# MorphingVCA.net
KiCad netlist of a schematic drawn in EAGLE
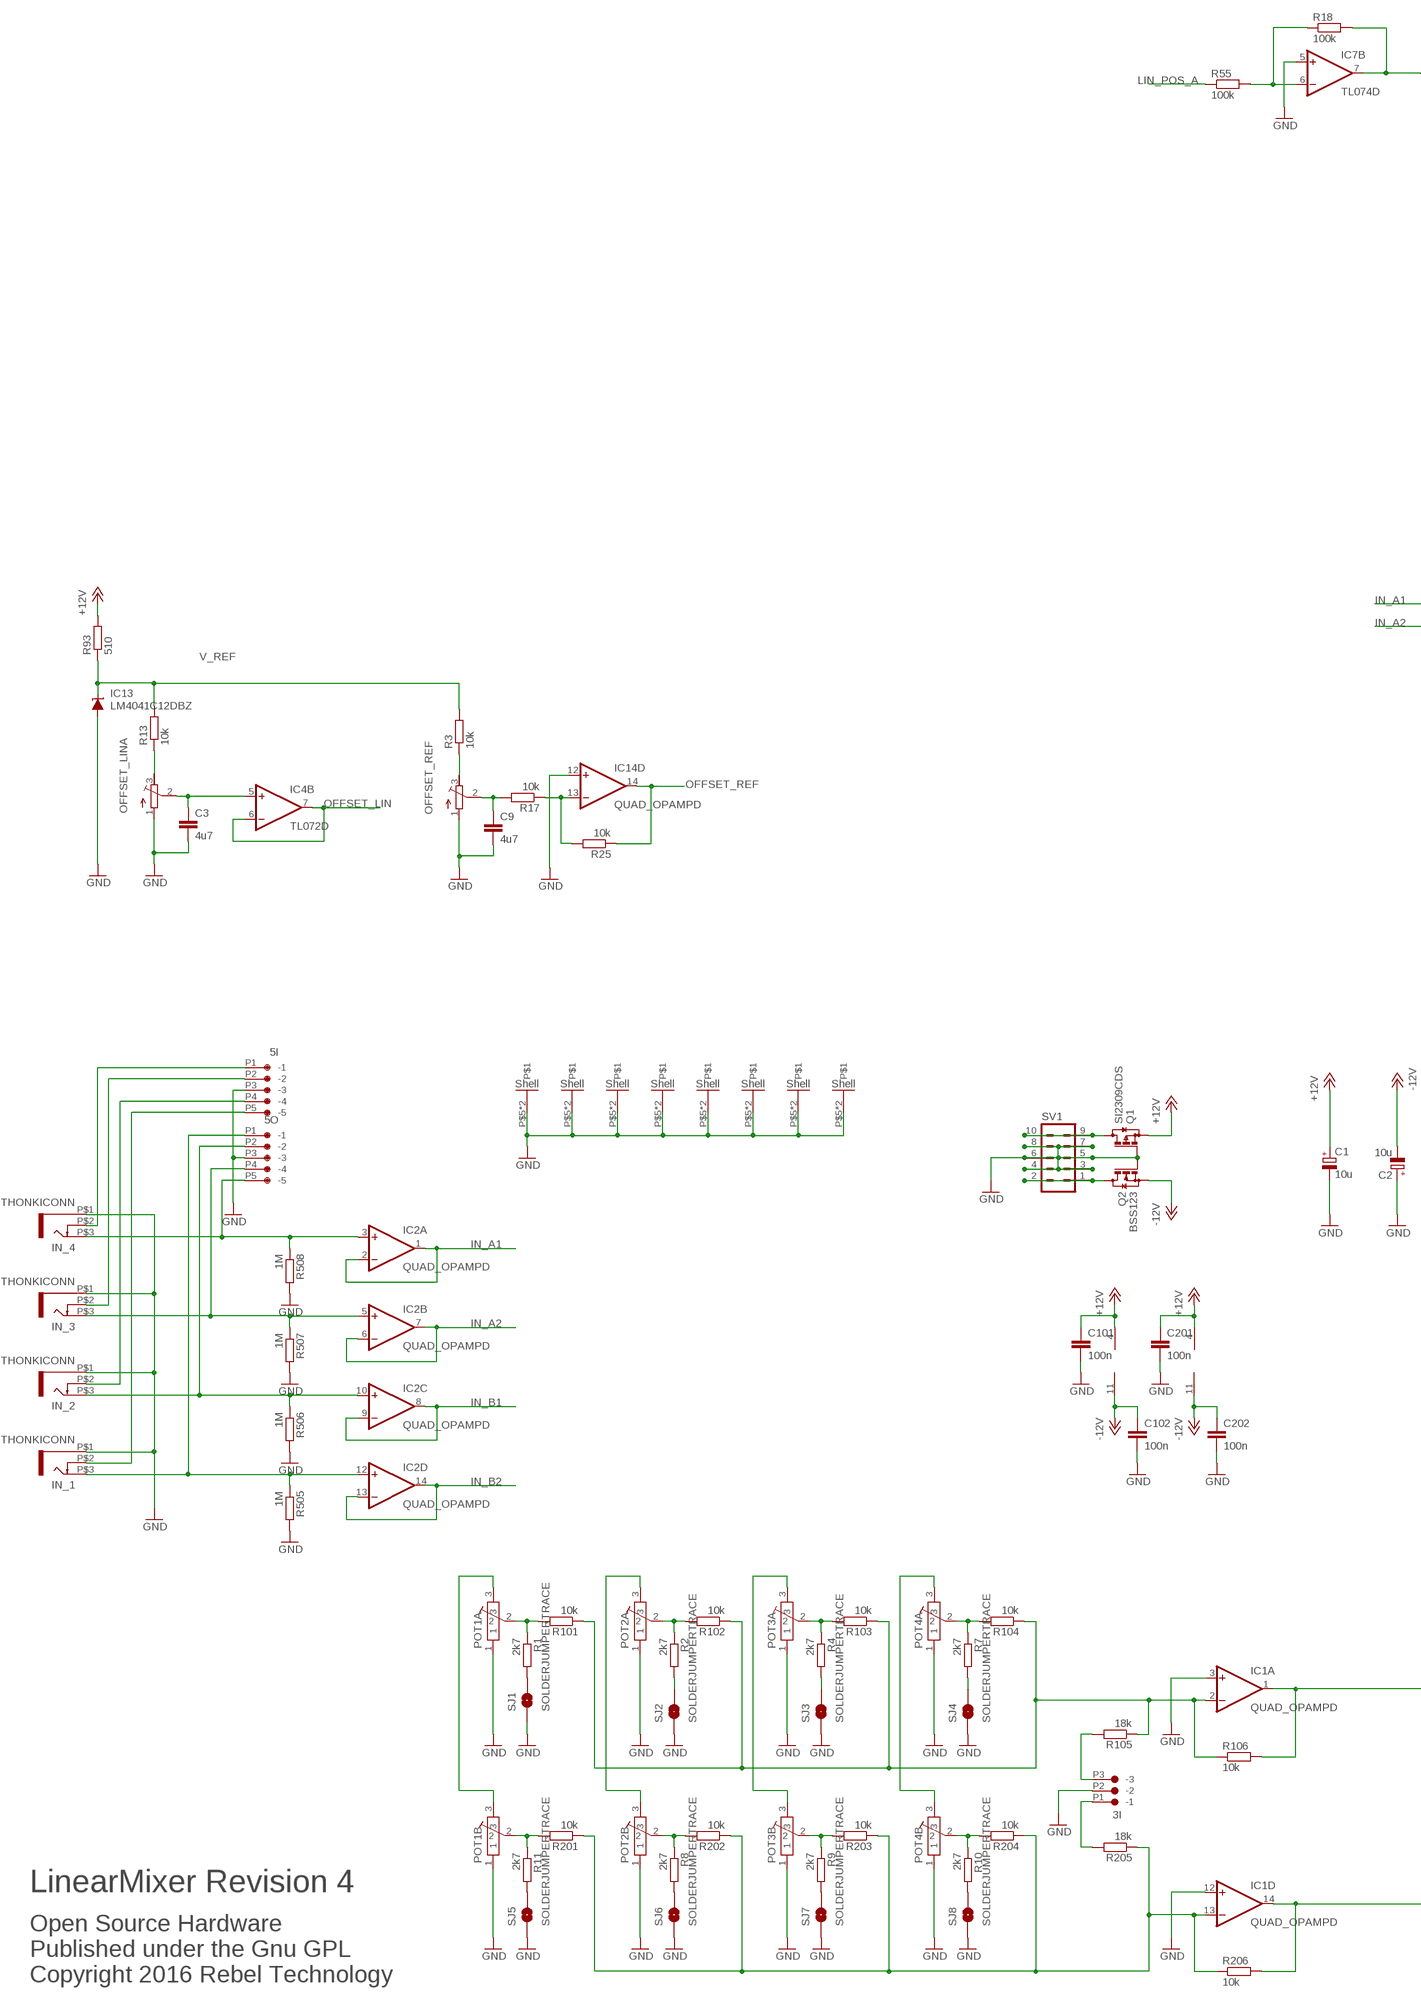
[diagram p0: schematic, sheet 1, part 1 of 2]
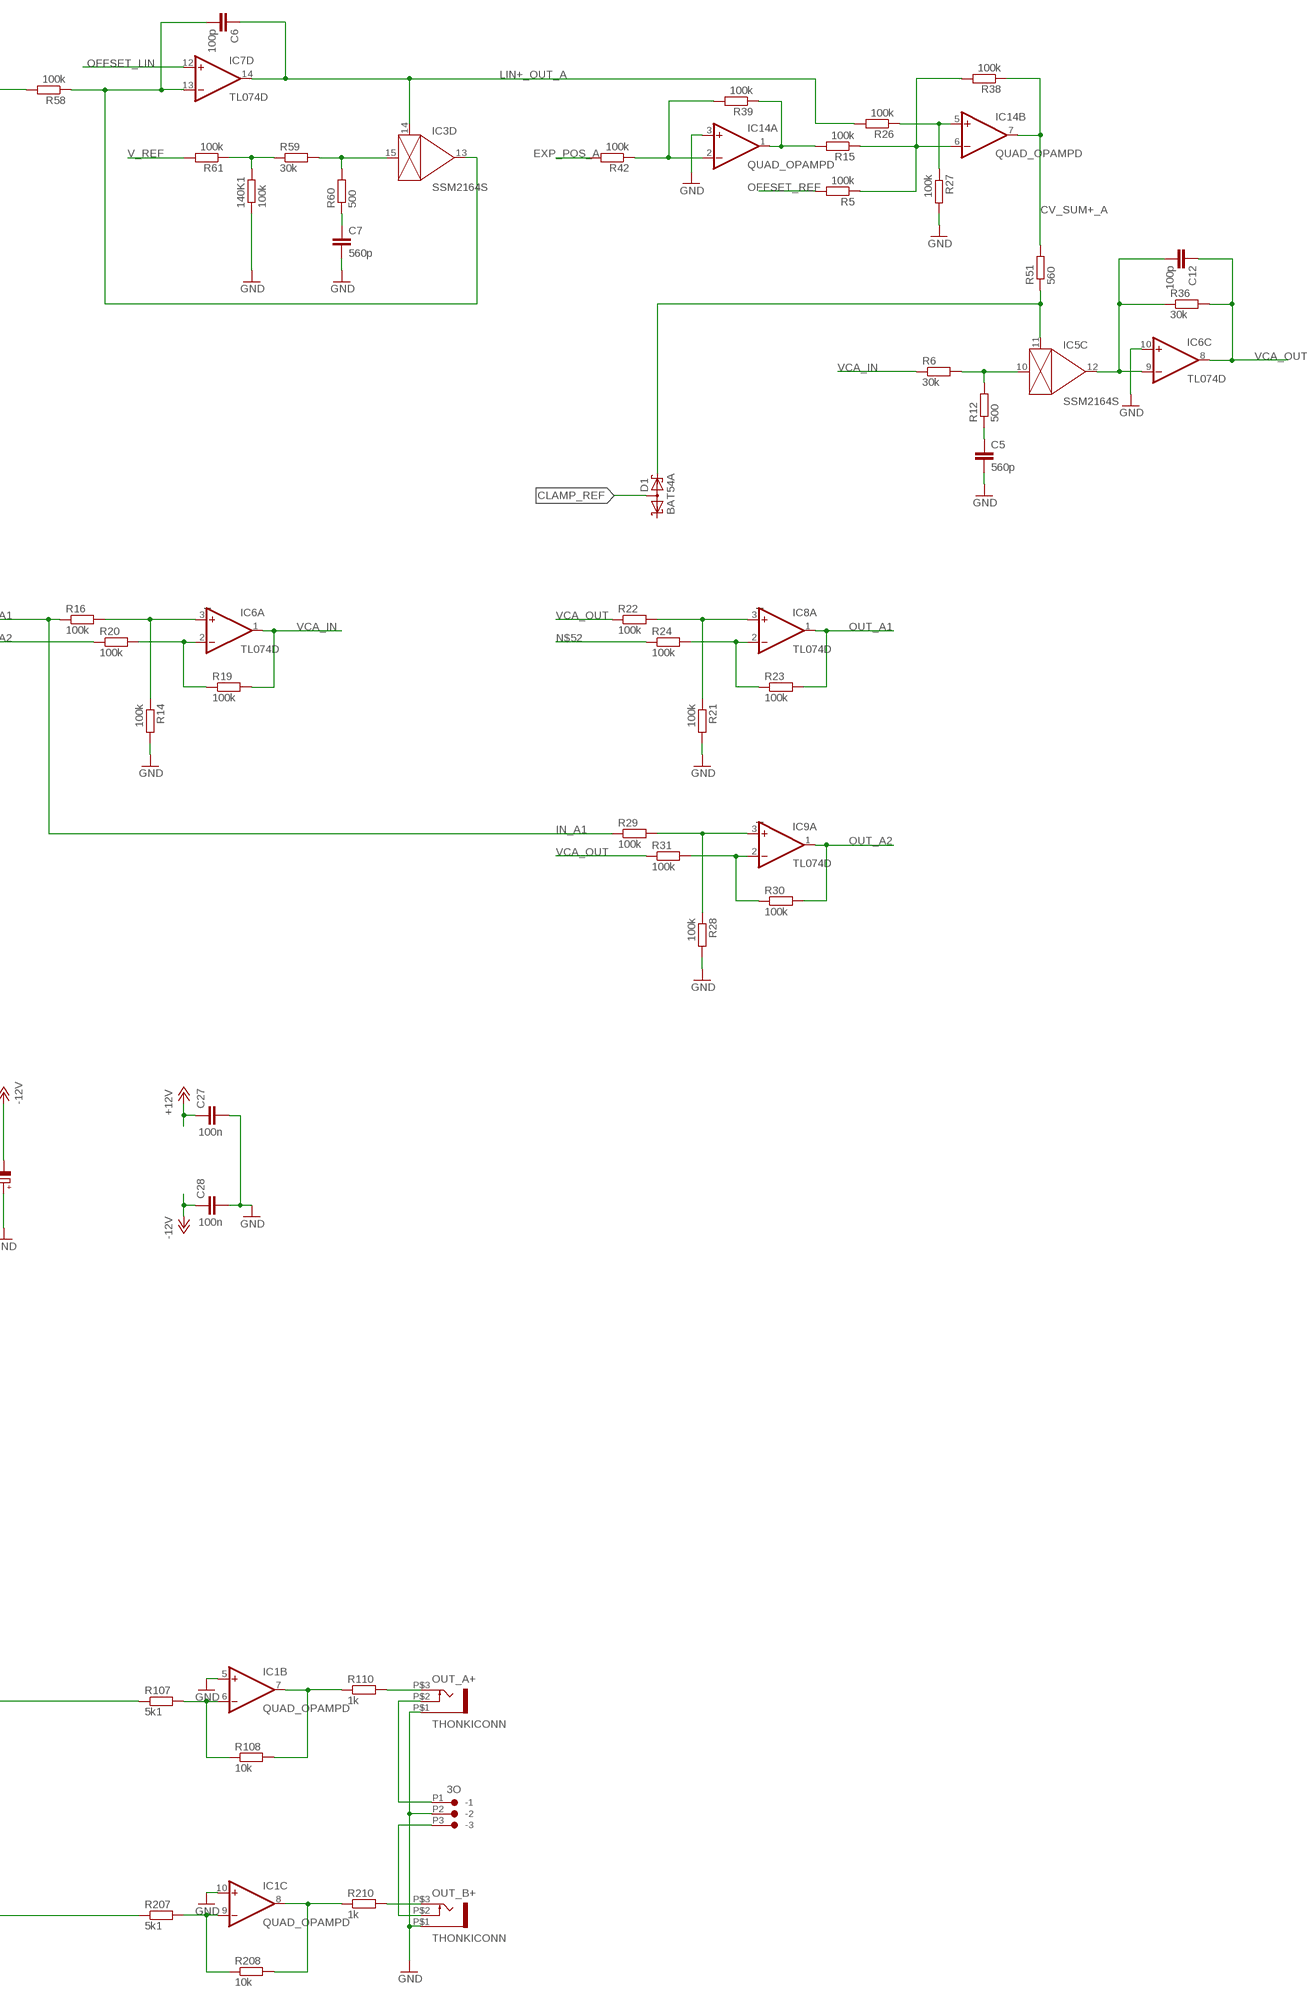
[diagram p1: schematic, sheet 1, part 2 of 2]

(export (version "E")
  (design (tool "Eeschema 10.0.6"))
  (components
    (comp (ref "3I")
      (value "CON-JST_PH_3W")
      (footprint "eagle-import:CON-JST_PH_3W")
      (libsource (lib "eagle-import") (part "CON-JST_PH_3W"))
    )
    (comp (ref "3O")
      (value "CON-JST_PH_3W")
      (footprint "eagle-import:CON-JST_PH_3W")
      (libsource (lib "eagle-import") (part "CON-JST_PH_3W"))
    )
    (comp (ref "5I")
      (value "CON-JST_PH_5W")
      (footprint "eagle-import:CON-JST_PH_5W")
      (libsource (lib "eagle-import") (part "CON-JST_PH_5W"))
    )
    (comp (ref "5O")
      (value "CON-JST_PH_5W")
      (footprint "eagle-import:CON-JST_PH_5W")
      (libsource (lib "eagle-import") (part "CON-JST_PH_5W"))
    )
    (comp (ref "140K1")
      (value "100k")
      (footprint "eagle-import:0603")
      (libsource (lib "eagle-import") (part "R-EU_0603"))
    )
    (comp (ref "C1")
      (value "10u")
      (footprint "eagle-import:153CLV-0505")
      (libsource (lib "eagle-import") (part "CPOL-EU153CLV-0505"))
    )
    (comp (ref "C2")
      (value "10u")
      (footprint "eagle-import:153CLV-0505")
      (libsource (lib "eagle-import") (part "CPOL-EU153CLV-0505"))
    )
    (comp (ref "C3")
      (value "4u7")
      (footprint "eagle-import:C0603K")
      (libsource (lib "eagle-import") (part "resistor_C-EUC0603K"))
    )
    (comp (ref "C5")
      (value "560p")
      (footprint "eagle-import:C0603K")
      (libsource (lib "eagle-import") (part "resistor_C-EUC0603K"))
    )
    (comp (ref "C6")
      (value "100p")
      (footprint "eagle-import:C0603K")
      (libsource (lib "eagle-import") (part "resistor_C-EUC0603K"))
    )
    (comp (ref "C7")
      (value "560p")
      (footprint "eagle-import:C0603K")
      (libsource (lib "eagle-import") (part "resistor_C-EUC0603K"))
    )
    (comp (ref "C9")
      (value "4u7")
      (footprint "eagle-import:C0603K")
      (libsource (lib "eagle-import") (part "resistor_C-EUC0603K"))
    )
    (comp (ref "C12")
      (value "100p")
      (footprint "eagle-import:C0603K")
      (libsource (lib "eagle-import") (part "resistor_C-EUC0603K"))
    )
    (comp (ref "C27")
      (value "100n")
      (footprint "eagle-import:C0603")
      (libsource (lib "eagle-import") (part "C-EUC0603"))
    )
    (comp (ref "C28")
      (value "100n")
      (footprint "eagle-import:C0603")
      (libsource (lib "eagle-import") (part "C-EUC0603"))
    )
    (comp (ref "C101")
      (value "100n")
      (footprint "eagle-import:C0603")
      (libsource (lib "eagle-import") (part "resistor_C-EUC0603"))
    )
    (comp (ref "C102")
      (value "100n")
      (footprint "eagle-import:C0603")
      (libsource (lib "eagle-import") (part "resistor_C-EUC0603"))
    )
    (comp (ref "C201")
      (value "100n")
      (footprint "eagle-import:C0603")
      (libsource (lib "eagle-import") (part "resistor_C-EUC0603"))
    )
    (comp (ref "C202")
      (value "100n")
      (footprint "eagle-import:C0603")
      (libsource (lib "eagle-import") (part "resistor_C-EUC0603"))
    )
    (comp (ref "D1")
      (value "BAT54A")
      (footprint "eagle-import:SOT23")
      (libsource (lib "eagle-import") (part "BAT54A"))
    )
    (comp (ref "IC1")
      (value "QUAD_OPAMPD")
      (footprint "eagle-import:SO14")
      (libsource (lib "eagle-import") (part "QUAD_OPAMPD"))
    )
    (comp (ref "IC2")
      (value "QUAD_OPAMPD")
      (footprint "eagle-import:SO14")
      (libsource (lib "eagle-import") (part "QUAD_OPAMPD"))
    )
    (comp (ref "IC3")
      (value "SSM2164S")
      (footprint "eagle-import:SOIC16N")
      (libsource (lib "eagle-import") (part "SSM2164S"))
    )
    (comp (ref "IC4")
      (value "TL072D")
      (footprint "eagle-import:SO08")
      (libsource (lib "eagle-import") (part "TL072D"))
    )
    (comp (ref "IC5")
      (value "SSM2164S")
      (footprint "eagle-import:SOIC16N")
      (fields (field (name "OC_FARNELL") "unknown"))
      (libsource (lib "eagle-import") (part "SSM2164S"))
    )
    (comp (ref "IC6")
      (value "TL074D")
      (footprint "eagle-import:SO14")
      (fields (field (name "OC_FARNELL") "unknown"))
      (libsource (lib "eagle-import") (part "TL074D"))
    )
    (comp (ref "IC7")
      (value "TL074D")
      (footprint "eagle-import:SO14")
      (fields (field (name "OC_FARNELL") "unknown"))
      (libsource (lib "eagle-import") (part "TL074D"))
    )
    (comp (ref "IC8")
      (value "TL074D")
      (footprint "eagle-import:SO14")
      (fields (field (name "OC_FARNELL") "unknown"))
      (libsource (lib "eagle-import") (part "TL074D"))
    )
    (comp (ref "IC9")
      (value "TL074D")
      (footprint "eagle-import:SO14")
      (fields (field (name "OC_FARNELL") "unknown"))
      (libsource (lib "eagle-import") (part "TL074D"))
    )
    (comp (ref "IC13")
      (value "LM4041C12DBZ")
      (footprint "eagle-import:DBZ_R-PDSO-G3")
      (fields (field (name "MF") "TEXAS INSTRUMENT CONNECTORS") (field (name "MPN") "LM4041C12QDBZT"))
      (libsource (lib "eagle-import") (part "LM4041DBZC12"))
    )
    (comp (ref "IC14")
      (value "QUAD_OPAMPD")
      (footprint "eagle-import:SO14")
      (libsource (lib "eagle-import") (part "QUAD_OPAMPD"))
    )
    (comp (ref "IN_1")
      (value "THONKICONN")
      (footprint "eagle-import:THONKICONN")
      (libsource (lib "eagle-import") (part "THONKICONN"))
    )
    (comp (ref "IN_2")
      (value "THONKICONN")
      (footprint "eagle-import:THONKICONN")
      (libsource (lib "eagle-import") (part "THONKICONN"))
    )
    (comp (ref "IN_3")
      (value "THONKICONN")
      (footprint "eagle-import:THONKICONN")
      (libsource (lib "eagle-import") (part "THONKICONN"))
    )
    (comp (ref "IN_4")
      (value "THONKICONN")
      (footprint "eagle-import:THONKICONN")
      (libsource (lib "eagle-import") (part "THONKICONN"))
    )
    (comp (ref "OFFSET_LINA")
      (value "R-TRIMM64W")
      (footprint "eagle-import:RTRIM64W")
      (libsource (lib "eagle-import") (part "R-TRIMM64W"))
    )
    (comp (ref "OFFSET_REF")
      (value "R-TRIMM64W")
      (footprint "eagle-import:RTRIM64W")
      (libsource (lib "eagle-import") (part "R-TRIMM64W"))
    )
    (comp (ref "OUT_A+")
      (value "THONKICONN")
      (footprint "eagle-import:THONKICONN")
      (libsource (lib "eagle-import") (part "THONKICONN"))
    )
    (comp (ref "OUT_B+")
      (value "THONKICONN")
      (footprint "eagle-import:THONKICONN")
      (libsource (lib "eagle-import") (part "THONKICONN"))
    )
    (comp (ref "POT1A")
      (value "POT-ALPS-RK09L1140")
      (footprint "eagle-import:POT-ALPS-RK09L1140")
      (libsource (lib "eagle-import") (part "POT-ALPS-RK09L1140"))
    )
    (comp (ref "POT1B")
      (value "POT-ALPS-RK09L1140")
      (footprint "eagle-import:POT-ALPS-RK09L1140")
      (libsource (lib "eagle-import") (part "POT-ALPS-RK09L1140"))
    )
    (comp (ref "POT2A")
      (value "POT-ALPS-RK09L1140")
      (footprint "eagle-import:POT-ALPS-RK09L1140")
      (libsource (lib "eagle-import") (part "POT-ALPS-RK09L1140"))
    )
    (comp (ref "POT2B")
      (value "POT-ALPS-RK09L1140")
      (footprint "eagle-import:POT-ALPS-RK09L1140")
      (libsource (lib "eagle-import") (part "POT-ALPS-RK09L1140"))
    )
    (comp (ref "POT3A")
      (value "POT-ALPS-RK09L1140")
      (footprint "eagle-import:POT-ALPS-RK09L1140")
      (libsource (lib "eagle-import") (part "POT-ALPS-RK09L1140"))
    )
    (comp (ref "POT3B")
      (value "POT-ALPS-RK09L1140")
      (footprint "eagle-import:POT-ALPS-RK09L1140")
      (libsource (lib "eagle-import") (part "POT-ALPS-RK09L1140"))
    )
    (comp (ref "POT4A")
      (value "POT-ALPS-RK09L1140")
      (footprint "eagle-import:POT-ALPS-RK09L1140")
      (libsource (lib "eagle-import") (part "POT-ALPS-RK09L1140"))
    )
    (comp (ref "POT4B")
      (value "POT-ALPS-RK09L1140")
      (footprint "eagle-import:POT-ALPS-RK09L1140")
      (libsource (lib "eagle-import") (part "POT-ALPS-RK09L1140"))
    )
    (comp (ref "Q1")
      (value "SI2309CDS")
      (footprint "eagle-import:SOT23")
      (libsource (lib "eagle-import") (part "BSS84"))
    )
    (comp (ref "Q2")
      (value "BSS123")
      (footprint "eagle-import:SOT23")
      (libsource (lib "eagle-import") (part "BSS123"))
    )
    (comp (ref "R1")
      (value "2k7")
      (footprint "eagle-import:R0603")
      (libsource (lib "eagle-import") (part "R-EU_R0603"))
    )
    (comp (ref "R2")
      (value "2k7")
      (footprint "eagle-import:R0603")
      (libsource (lib "eagle-import") (part "R-EU_R0603"))
    )
    (comp (ref "R3")
      (value "10k")
      (footprint "eagle-import:0603")
      (libsource (lib "eagle-import") (part "R-EU_0603"))
    )
    (comp (ref "R4")
      (value "2k7")
      (footprint "eagle-import:R0603")
      (libsource (lib "eagle-import") (part "R-EU_R0603"))
    )
    (comp (ref "R5")
      (value "100k")
      (footprint "eagle-import:0603")
      (libsource (lib "eagle-import") (part "R-EU_0603"))
    )
    (comp (ref "R6")
      (value "30k")
      (footprint "eagle-import:0603")
      (libsource (lib "eagle-import") (part "R-EU_0603"))
    )
    (comp (ref "R7")
      (value "2k7")
      (footprint "eagle-import:R0603")
      (libsource (lib "eagle-import") (part "R-EU_R0603"))
    )
    (comp (ref "R8")
      (value "2k7")
      (footprint "eagle-import:R0603")
      (libsource (lib "eagle-import") (part "R-EU_R0603"))
    )
    (comp (ref "R9")
      (value "2k7")
      (footprint "eagle-import:R0603")
      (libsource (lib "eagle-import") (part "R-EU_R0603"))
    )
    (comp (ref "R10")
      (value "2k7")
      (footprint "eagle-import:R0603")
      (libsource (lib "eagle-import") (part "R-EU_R0603"))
    )
    (comp (ref "R11")
      (value "2k7")
      (footprint "eagle-import:R0603")
      (libsource (lib "eagle-import") (part "R-EU_R0603"))
    )
    (comp (ref "R12")
      (value "500")
      (footprint "eagle-import:0603")
      (libsource (lib "eagle-import") (part "R-EU_0603"))
    )
    (comp (ref "R13")
      (value "10k")
      (footprint "eagle-import:0603")
      (libsource (lib "eagle-import") (part "R-EU_0603"))
    )
    (comp (ref "R14")
      (value "100k")
      (footprint "eagle-import:0603")
      (libsource (lib "eagle-import") (part "R-EU_0603"))
    )
    (comp (ref "R15")
      (value "100k")
      (footprint "eagle-import:0603")
      (libsource (lib "eagle-import") (part "R-EU_0603"))
    )
    (comp (ref "R16")
      (value "100k")
      (footprint "eagle-import:0603")
      (libsource (lib "eagle-import") (part "R-EU_0603"))
    )
    (comp (ref "R17")
      (value "10k")
      (footprint "eagle-import:0603")
      (libsource (lib "eagle-import") (part "R-EU_0603"))
    )
    (comp (ref "R18")
      (value "100k")
      (footprint "eagle-import:0603")
      (libsource (lib "eagle-import") (part "R-EU_0603"))
    )
    (comp (ref "R19")
      (value "100k")
      (footprint "eagle-import:0603")
      (libsource (lib "eagle-import") (part "R-EU_0603"))
    )
    (comp (ref "R20")
      (value "100k")
      (footprint "eagle-import:0603")
      (libsource (lib "eagle-import") (part "R-EU_0603"))
    )
    (comp (ref "R21")
      (value "100k")
      (footprint "eagle-import:0603")
      (libsource (lib "eagle-import") (part "R-EU_0603"))
    )
    (comp (ref "R22")
      (value "100k")
      (footprint "eagle-import:0603")
      (libsource (lib "eagle-import") (part "R-EU_0603"))
    )
    (comp (ref "R23")
      (value "100k")
      (footprint "eagle-import:0603")
      (libsource (lib "eagle-import") (part "R-EU_0603"))
    )
    (comp (ref "R24")
      (value "100k")
      (footprint "eagle-import:0603")
      (libsource (lib "eagle-import") (part "R-EU_0603"))
    )
    (comp (ref "R25")
      (value "10k")
      (footprint "eagle-import:0603")
      (libsource (lib "eagle-import") (part "R-EU_0603"))
    )
    (comp (ref "R26")
      (value "100k")
      (footprint "eagle-import:0603")
      (libsource (lib "eagle-import") (part "R-EU_0603"))
    )
    (comp (ref "R27")
      (value "100k")
      (footprint "eagle-import:0603")
      (libsource (lib "eagle-import") (part "R-EU_0603"))
    )
    (comp (ref "R28")
      (value "100k")
      (footprint "eagle-import:0603")
      (libsource (lib "eagle-import") (part "R-EU_0603"))
    )
    (comp (ref "R29")
      (value "100k")
      (footprint "eagle-import:0603")
      (libsource (lib "eagle-import") (part "R-EU_0603"))
    )
    (comp (ref "R30")
      (value "100k")
      (footprint "eagle-import:0603")
      (libsource (lib "eagle-import") (part "R-EU_0603"))
    )
    (comp (ref "R31")
      (value "100k")
      (footprint "eagle-import:0603")
      (libsource (lib "eagle-import") (part "R-EU_0603"))
    )
    (comp (ref "R36")
      (value "30k")
      (footprint "eagle-import:0603")
      (libsource (lib "eagle-import") (part "R-EU_0603"))
    )
    (comp (ref "R38")
      (value "100k")
      (footprint "eagle-import:0603")
      (libsource (lib "eagle-import") (part "R-EU_0603"))
    )
    (comp (ref "R39")
      (value "100k")
      (footprint "eagle-import:0603")
      (libsource (lib "eagle-import") (part "R-EU_0603"))
    )
    (comp (ref "R42")
      (value "100k")
      (footprint "eagle-import:0603")
      (libsource (lib "eagle-import") (part "R-EU_0603"))
    )
    (comp (ref "R51")
      (value "560")
      (footprint "eagle-import:0603")
      (libsource (lib "eagle-import") (part "R-EU_0603"))
    )
    (comp (ref "R55")
      (value "100k")
      (footprint "eagle-import:0603")
      (libsource (lib "eagle-import") (part "R-EU_0603"))
    )
    (comp (ref "R58")
      (value "100k")
      (footprint "eagle-import:0603")
      (libsource (lib "eagle-import") (part "R-EU_0603"))
    )
    (comp (ref "R59")
      (value "30k")
      (footprint "eagle-import:0603")
      (libsource (lib "eagle-import") (part "R-EU_0603"))
    )
    (comp (ref "R60")
      (value "500")
      (footprint "eagle-import:0603")
      (libsource (lib "eagle-import") (part "R-EU_0603"))
    )
    (comp (ref "R61")
      (value "100k")
      (footprint "eagle-import:0603")
      (libsource (lib "eagle-import") (part "R-EU_0603"))
    )
    (comp (ref "R93")
      (value "510")
      (footprint "eagle-import:0603")
      (libsource (lib "eagle-import") (part "R-EU_0603"))
    )
    (comp (ref "R101")
      (value "10k")
      (footprint "eagle-import:R0603")
      (libsource (lib "eagle-import") (part "R-EU_R0603"))
    )
    (comp (ref "R102")
      (value "10k")
      (footprint "eagle-import:R0603")
      (libsource (lib "eagle-import") (part "R-EU_R0603"))
    )
    (comp (ref "R103")
      (value "10k")
      (footprint "eagle-import:R0603")
      (libsource (lib "eagle-import") (part "R-EU_R0603"))
    )
    (comp (ref "R104")
      (value "10k")
      (footprint "eagle-import:R0603")
      (libsource (lib "eagle-import") (part "R-EU_R0603"))
    )
    (comp (ref "R105")
      (value "18k")
      (footprint "eagle-import:R0603")
      (libsource (lib "eagle-import") (part "R-EU_R0603"))
    )
    (comp (ref "R106")
      (value "10k")
      (footprint "eagle-import:R0603")
      (libsource (lib "eagle-import") (part "R-EU_R0603"))
    )
    (comp (ref "R107")
      (value "5k1")
      (footprint "eagle-import:R0603")
      (libsource (lib "eagle-import") (part "R-EU_R0603"))
    )
    (comp (ref "R108")
      (value "10k")
      (footprint "eagle-import:R0603")
      (libsource (lib "eagle-import") (part "R-EU_R0603"))
    )
    (comp (ref "R110")
      (value "1k")
      (footprint "eagle-import:R0603")
      (libsource (lib "eagle-import") (part "R-EU_R0603"))
    )
    (comp (ref "R201")
      (value "10k")
      (footprint "eagle-import:R0603")
      (libsource (lib "eagle-import") (part "R-EU_R0603"))
    )
    (comp (ref "R202")
      (value "10k")
      (footprint "eagle-import:R0603")
      (libsource (lib "eagle-import") (part "R-EU_R0603"))
    )
    (comp (ref "R203")
      (value "10k")
      (footprint "eagle-import:R0603")
      (libsource (lib "eagle-import") (part "R-EU_R0603"))
    )
    (comp (ref "R204")
      (value "10k")
      (footprint "eagle-import:R0603")
      (libsource (lib "eagle-import") (part "R-EU_R0603"))
    )
    (comp (ref "R205")
      (value "18k")
      (footprint "eagle-import:R0603")
      (libsource (lib "eagle-import") (part "R-EU_R0603"))
    )
    (comp (ref "R206")
      (value "10k")
      (footprint "eagle-import:R0603")
      (libsource (lib "eagle-import") (part "R-EU_R0603"))
    )
    (comp (ref "R207")
      (value "5k1")
      (footprint "eagle-import:R0603")
      (libsource (lib "eagle-import") (part "R-EU_R0603"))
    )
    (comp (ref "R208")
      (value "10k")
      (footprint "eagle-import:R0603")
      (libsource (lib "eagle-import") (part "R-EU_R0603"))
    )
    (comp (ref "R210")
      (value "1k")
      (footprint "eagle-import:R0603")
      (libsource (lib "eagle-import") (part "R-EU_R0603"))
    )
    (comp (ref "R505")
      (value "1M")
      (footprint "eagle-import:R0603")
      (libsource (lib "eagle-import") (part "R-EU_R0603"))
    )
    (comp (ref "R506")
      (value "1M")
      (footprint "eagle-import:R0603")
      (libsource (lib "eagle-import") (part "R-EU_R0603"))
    )
    (comp (ref "R507")
      (value "1M")
      (footprint "eagle-import:R0603")
      (libsource (lib "eagle-import") (part "R-EU_R0603"))
    )
    (comp (ref "R508")
      (value "1M")
      (footprint "eagle-import:R0603")
      (libsource (lib "eagle-import") (part "R-EU_R0603"))
    )
    (comp (ref "SJ1")
      (value "SOLDERJUMPERTRACE")
      (footprint "eagle-import:SJ_2S-TRACE")
      (libsource (lib "eagle-import") (part "SOLDERJUMPERTRACE"))
    )
    (comp (ref "SJ2")
      (value "SOLDERJUMPERTRACE")
      (footprint "eagle-import:SJ_2S-TRACE")
      (libsource (lib "eagle-import") (part "SOLDERJUMPERTRACE"))
    )
    (comp (ref "SJ3")
      (value "SOLDERJUMPERTRACE")
      (footprint "eagle-import:SJ_2S-TRACE")
      (libsource (lib "eagle-import") (part "SOLDERJUMPERTRACE"))
    )
    (comp (ref "SJ4")
      (value "SOLDERJUMPERTRACE")
      (footprint "eagle-import:SJ_2S-TRACE")
      (libsource (lib "eagle-import") (part "SOLDERJUMPERTRACE"))
    )
    (comp (ref "SJ5")
      (value "SOLDERJUMPERTRACE")
      (footprint "eagle-import:SJ_2S-TRACE")
      (libsource (lib "eagle-import") (part "SOLDERJUMPERTRACE"))
    )
    (comp (ref "SJ6")
      (value "SOLDERJUMPERTRACE")
      (footprint "eagle-import:SJ_2S-TRACE")
      (libsource (lib "eagle-import") (part "SOLDERJUMPERTRACE"))
    )
    (comp (ref "SJ7")
      (value "SOLDERJUMPERTRACE")
      (footprint "eagle-import:SJ_2S-TRACE")
      (libsource (lib "eagle-import") (part "SOLDERJUMPERTRACE"))
    )
    (comp (ref "SJ8")
      (value "SOLDERJUMPERTRACE")
      (footprint "eagle-import:SJ_2S-TRACE")
      (libsource (lib "eagle-import") (part "SOLDERJUMPERTRACE"))
    )
    (comp (ref "SV1")
      (value "MA05-2")
      (footprint "eagle-import:MA05-2")
      (libsource (lib "eagle-import") (part "MA05-2"))
    )
  )
  (nets
    (net (code "1") (name "+12V") (class "Default")
      (node (ref "C1") (pin "+") (pinfunction "+_+") (pintype "passive"))
      (node (ref "C101") (pin "1") (pinfunction "1_1") (pintype "passive"))
      (node (ref "C201") (pin "1") (pinfunction "1_1") (pintype "passive"))
      (node (ref "C27") (pin "1") (pinfunction "1_1") (pintype "passive"))
      (node (ref "IC1") (pin "4") (pinfunction "V+_4") (pintype "power_in"))
      (node (ref "IC2") (pin "4") (pinfunction "V+_4") (pintype "power_in"))
      (node (ref "Q1") (pin "2") (pinfunction "S_2") (pintype "passive"))
      (node (ref "R93") (pin "2") (pinfunction "2_2") (pintype "passive"))
    )
    (net (code "2") (name "-12V") (class "Default")
      (node (ref "C102") (pin "1") (pinfunction "1_1") (pintype "passive"))
      (node (ref "C2") (pin "-") (pinfunction "-_-") (pintype "passive"))
      (node (ref "C202") (pin "1") (pinfunction "1_1") (pintype "passive"))
      (node (ref "C28") (pin "1") (pinfunction "1_1") (pintype "passive"))
      (node (ref "IC1") (pin "11") (pinfunction "V-_11") (pintype "power_in"))
      (node (ref "IC2") (pin "11") (pinfunction "V-_11") (pintype "power_in"))
      (node (ref "Q2") (pin "2") (pinfunction "S_2") (pintype "passive"))
    )
    (net (code "3") (name "/CV_SUM+_A") (class "Default")
      (node (ref "IC14") (pin "7") (pinfunction "OUT_7") (pintype "output"))
      (node (ref "R38") (pin "1") (pinfunction "1_1") (pintype "passive"))
      (node (ref "R51") (pin "2") (pinfunction "2_2") (pintype "passive"))
    )
    (net (code "4") (name "/EXP_POS_A") (class "Default")
      (node (ref "R42") (pin "2") (pinfunction "2_2") (pintype "passive"))
    )
    (net (code "5") (name "/IN_A1") (class "Default")
      (node (ref "IC2") (pin "1") (pinfunction "OUT_1") (pintype "output"))
      (node (ref "IC2") (pin "2") (pinfunction "-IN_2") (pintype "input"))
      (node (ref "R16") (pin "1") (pinfunction "1_1") (pintype "passive"))
      (node (ref "R29") (pin "1") (pinfunction "1_1") (pintype "passive"))
    )
    (net (code "6") (name "/IN_A2") (class "Default")
      (node (ref "IC2") (pin "6") (pinfunction "-IN_6") (pintype "input"))
      (node (ref "IC2") (pin "7") (pinfunction "OUT_7") (pintype "output"))
      (node (ref "R20") (pin "1") (pinfunction "1_1") (pintype "passive"))
    )
    (net (code "7") (name "/IN_B1") (class "Default")
      (node (ref "IC2") (pin "8") (pinfunction "OUT_8") (pintype "output"))
      (node (ref "IC2") (pin "9") (pinfunction "-IN_9") (pintype "input"))
    )
    (net (code "8") (name "/IN_B2") (class "Default")
      (node (ref "IC2") (pin "13") (pinfunction "-IN_13") (pintype "input"))
      (node (ref "IC2") (pin "14") (pinfunction "OUT_14") (pintype "output"))
    )
    (net (code "9") (name "/LIN+_OUT_A") (class "Default")
      (node (ref "C6") (pin "1") (pinfunction "1_1") (pintype "passive"))
      (node (ref "IC3") (pin "14") (pinfunction "CTRL_14") (pintype "input"))
      (node (ref "IC7") (pin "14") (pinfunction "OUT_14") (pintype "output"))
      (node (ref "R26") (pin "2") (pinfunction "2_2") (pintype "passive"))
    )
    (net (code "10") (name "/LIN_POS_A") (class "Default")
      (node (ref "R55") (pin "1") (pinfunction "1_1") (pintype "passive"))
    )
    (net (code "11") (name "/N$52") (class "Default")
      (node (ref "R24") (pin "1") (pinfunction "1_1") (pintype "passive"))
    )
    (net (code "12") (name "/OFFSET_LIN") (class "Default")
      (node (ref "IC4") (pin "6") (pinfunction "-IN_6") (pintype "input"))
      (node (ref "IC4") (pin "7") (pinfunction "OUT_7") (pintype "output"))
      (node (ref "IC7") (pin "12") (pinfunction "+IN_12") (pintype "input"))
    )
    (net (code "13") (name "/OFFSET_REF") (class "Default")
      (node (ref "IC14") (pin "14") (pinfunction "OUT_14") (pintype "output"))
      (node (ref "R25") (pin "1") (pinfunction "1_1") (pintype "passive"))
      (node (ref "R5") (pin "2") (pinfunction "2_2") (pintype "passive"))
    )
    (net (code "14") (name "/OUT_A1") (class "Default")
      (node (ref "IC8") (pin "1") (pinfunction "OUT_1") (pintype "output"))
      (node (ref "R23") (pin "2") (pinfunction "2_2") (pintype "passive"))
    )
    (net (code "15") (name "/OUT_A2") (class "Default")
      (node (ref "IC9") (pin "1") (pinfunction "OUT_1") (pintype "output"))
      (node (ref "R30") (pin "2") (pinfunction "2_2") (pintype "passive"))
    )
    (net (code "16") (name "/VCA_IN") (class "Default")
      (node (ref "IC6") (pin "1") (pinfunction "OUT_1") (pintype "output"))
      (node (ref "R19") (pin "2") (pinfunction "2_2") (pintype "passive"))
      (node (ref "R6") (pin "1") (pinfunction "1_1") (pintype "passive"))
    )
    (net (code "17") (name "/VCA_OUT") (class "Default")
      (node (ref "C12") (pin "1") (pinfunction "1_1") (pintype "passive"))
      (node (ref "IC6") (pin "8") (pinfunction "OUT_8") (pintype "output"))
      (node (ref "R22") (pin "1") (pinfunction "1_1") (pintype "passive"))
      (node (ref "R31") (pin "1") (pinfunction "1_1") (pintype "passive"))
      (node (ref "R36") (pin "2") (pinfunction "2_2") (pintype "passive"))
    )
    (net (code "18") (name "/V_REF") (class "Default")
      (node (ref "IC13") (pin "1") (pinfunction "C_1") (pintype "passive"))
      (node (ref "R13") (pin "2") (pinfunction "2_2") (pintype "passive"))
      (node (ref "R3") (pin "2") (pinfunction "2_2") (pintype "passive"))
      (node (ref "R61") (pin "2") (pinfunction "2_2") (pintype "passive"))
      (node (ref "R93") (pin "1") (pinfunction "1_1") (pintype "passive"))
    )
    (net (code "19") (name "CLAMP_REF") (class "Default")
      (node (ref "D1") (pin "3") (pinfunction "AA_3") (pintype "passive"))
    )
    (net (code "20") (name "GND") (class "Default")
      (node (ref "140K1") (pin "1") (pinfunction "1_1") (pintype "passive"))
      (node (ref "3I") (pin "P2") (pinfunction "-2_P2") (pintype "bidirectional"))
      (node (ref "3O") (pin "P2") (pinfunction "-2_P2") (pintype "bidirectional"))
      (node (ref "5I") (pin "P3") (pinfunction "-3_P3") (pintype "bidirectional"))
      (node (ref "5O") (pin "P3") (pinfunction "-3_P3") (pintype "bidirectional"))
      (node (ref "C1") (pin "-") (pinfunction "-_-") (pintype "passive"))
      (node (ref "C101") (pin "2") (pinfunction "2_2") (pintype "passive"))
      (node (ref "C102") (pin "2") (pinfunction "2_2") (pintype "passive"))
      (node (ref "C2") (pin "+") (pinfunction "+_+") (pintype "passive"))
      (node (ref "C201") (pin "2") (pinfunction "2_2") (pintype "passive"))
      (node (ref "C202") (pin "2") (pinfunction "2_2") (pintype "passive"))
      (node (ref "C27") (pin "2") (pinfunction "2_2") (pintype "passive"))
      (node (ref "C28") (pin "2") (pinfunction "2_2") (pintype "passive"))
      (node (ref "C3") (pin "2") (pinfunction "2_2") (pintype "passive"))
      (node (ref "C5") (pin "2") (pinfunction "2_2") (pintype "passive"))
      (node (ref "C7") (pin "2") (pinfunction "2_2") (pintype "passive"))
      (node (ref "C9") (pin "2") (pinfunction "2_2") (pintype "passive"))
      (node (ref "IC1") (pin "10") (pinfunction "+IN_10") (pintype "input"))
      (node (ref "IC1") (pin "12") (pinfunction "+IN_12") (pintype "input"))
      (node (ref "IC1") (pin "3") (pinfunction "+IN_3") (pintype "input"))
      (node (ref "IC1") (pin "5") (pinfunction "+IN_5") (pintype "input"))
      (node (ref "IC13") (pin "2") (pinfunction "A_2") (pintype "passive"))
      (node (ref "IC14") (pin "12") (pinfunction "+IN_12") (pintype "input"))
      (node (ref "IC14") (pin "3") (pinfunction "+IN_3") (pintype "input"))
      (node (ref "IC6") (pin "10") (pinfunction "+IN_10") (pintype "input"))
      (node (ref "IC7") (pin "5") (pinfunction "+IN_5") (pintype "input"))
      (node (ref "IN_1") (pin "P$1") (pinfunction "5_P$1") (pintype "passive"))
      (node (ref "IN_2") (pin "P$1") (pinfunction "5_P$1") (pintype "passive"))
      (node (ref "IN_3") (pin "P$1") (pinfunction "5_P$1") (pintype "passive"))
      (node (ref "IN_4") (pin "P$1") (pinfunction "5_P$1") (pintype "passive"))
      (node (ref "OFFSET_LINA") (pin "1") (pinfunction "A_1") (pintype "passive"))
      (node (ref "OFFSET_REF") (pin "1") (pinfunction "A_1") (pintype "passive"))
      (node (ref "OUT_A+") (pin "P$1") (pinfunction "5_P$1") (pintype "passive"))
      (node (ref "OUT_B+") (pin "P$1") (pinfunction "5_P$1") (pintype "passive"))
      (node (ref "POT1A") (pin "1") (pinfunction "1_1") (pintype "bidirectional"))
      (node (ref "POT1A") (pin "P$5") (pinfunction "P$1_P$5") (pintype "bidirectional"))
      (node (ref "POT1A") (pin "P$6") (pinfunction "P$1_P$6") (pintype "bidirectional"))
      (node (ref "POT1B") (pin "1") (pinfunction "1_1") (pintype "bidirectional"))
      (node (ref "POT1B") (pin "P$5") (pinfunction "P$1_P$5") (pintype "bidirectional"))
      (node (ref "POT1B") (pin "P$6") (pinfunction "P$1_P$6") (pintype "bidirectional"))
      (node (ref "POT2A") (pin "1") (pinfunction "1_1") (pintype "bidirectional"))
      (node (ref "POT2A") (pin "P$5") (pinfunction "P$1_P$5") (pintype "bidirectional"))
      (node (ref "POT2A") (pin "P$6") (pinfunction "P$1_P$6") (pintype "bidirectional"))
      (node (ref "POT2B") (pin "1") (pinfunction "1_1") (pintype "bidirectional"))
      (node (ref "POT2B") (pin "P$5") (pinfunction "P$1_P$5") (pintype "bidirectional"))
      (node (ref "POT2B") (pin "P$6") (pinfunction "P$1_P$6") (pintype "bidirectional"))
      (node (ref "POT3A") (pin "1") (pinfunction "1_1") (pintype "bidirectional"))
      (node (ref "POT3A") (pin "P$5") (pinfunction "P$1_P$5") (pintype "bidirectional"))
      (node (ref "POT3A") (pin "P$6") (pinfunction "P$1_P$6") (pintype "bidirectional"))
      (node (ref "POT3B") (pin "1") (pinfunction "1_1") (pintype "bidirectional"))
      (node (ref "POT3B") (pin "P$5") (pinfunction "P$1_P$5") (pintype "bidirectional"))
      (node (ref "POT3B") (pin "P$6") (pinfunction "P$1_P$6") (pintype "bidirectional"))
      (node (ref "POT4A") (pin "1") (pinfunction "1_1") (pintype "bidirectional"))
      (node (ref "POT4A") (pin "P$5") (pinfunction "P$1_P$5") (pintype "bidirectional"))
      (node (ref "POT4A") (pin "P$6") (pinfunction "P$1_P$6") (pintype "bidirectional"))
      (node (ref "POT4B") (pin "1") (pinfunction "1_1") (pintype "bidirectional"))
      (node (ref "POT4B") (pin "P$5") (pinfunction "P$1_P$5") (pintype "bidirectional"))
      (node (ref "POT4B") (pin "P$6") (pinfunction "P$1_P$6") (pintype "bidirectional"))
      (node (ref "Q1") (pin "1") (pinfunction "G_1") (pintype "passive"))
      (node (ref "Q2") (pin "1") (pinfunction "G_1") (pintype "passive"))
      (node (ref "R14") (pin "2") (pinfunction "2_2") (pintype "passive"))
      (node (ref "R21") (pin "2") (pinfunction "2_2") (pintype "passive"))
      (node (ref "R27") (pin "2") (pinfunction "2_2") (pintype "passive"))
      (node (ref "R28") (pin "2") (pinfunction "2_2") (pintype "passive"))
      (node (ref "R505") (pin "2") (pinfunction "2_2") (pintype "passive"))
      (node (ref "R506") (pin "2") (pinfunction "2_2") (pintype "passive"))
      (node (ref "R507") (pin "2") (pinfunction "2_2") (pintype "passive"))
      (node (ref "R508") (pin "2") (pinfunction "2_2") (pintype "passive"))
      (node (ref "SJ1") (pin "1") (pinfunction "1_1") (pintype "passive"))
      (node (ref "SJ2") (pin "1") (pinfunction "1_1") (pintype "passive"))
      (node (ref "SJ3") (pin "1") (pinfunction "1_1") (pintype "passive"))
      (node (ref "SJ4") (pin "1") (pinfunction "1_1") (pintype "passive"))
      (node (ref "SJ5") (pin "1") (pinfunction "1_1") (pintype "passive"))
      (node (ref "SJ6") (pin "1") (pinfunction "1_1") (pintype "passive"))
      (node (ref "SJ7") (pin "1") (pinfunction "1_1") (pintype "passive"))
      (node (ref "SJ8") (pin "1") (pinfunction "1_1") (pintype "passive"))
      (node (ref "SV1") (pin "3") (pinfunction "3_3") (pintype "passive"))
      (node (ref "SV1") (pin "4") (pinfunction "4_4") (pintype "passive"))
      (node (ref "SV1") (pin "5") (pinfunction "5_5") (pintype "passive"))
      (node (ref "SV1") (pin "6") (pinfunction "6_6") (pintype "passive"))
      (node (ref "SV1") (pin "7") (pinfunction "7_7") (pintype "passive"))
      (node (ref "SV1") (pin "8") (pinfunction "8_8") (pintype "passive"))
    )
    (net (code "21") (name "Net-(3I--1)") (class "Default")
      (node (ref "3I") (pin "P1") (pinfunction "-1_P1") (pintype "bidirectional"))
      (node (ref "R205") (pin "2") (pinfunction "2_2") (pintype "passive"))
    )
    (net (code "22") (name "Net-(3I--3)") (class "Default")
      (node (ref "3I") (pin "P3") (pinfunction "-3_P3") (pintype "bidirectional"))
      (node (ref "R105") (pin "2") (pinfunction "2_2") (pintype "passive"))
    )
    (net (code "23") (name "Net-(3O--1)") (class "Default")
      (node (ref "3O") (pin "P1") (pinfunction "-1_P1") (pintype "bidirectional"))
      (node (ref "OUT_A+") (pin "P$2") (pinfunction "4_P$2") (pintype "passive"))
    )
    (net (code "24") (name "Net-(3O--3)") (class "Default")
      (node (ref "3O") (pin "P3") (pinfunction "-3_P3") (pintype "bidirectional"))
      (node (ref "OUT_B+") (pin "P$2") (pinfunction "4_P$2") (pintype "passive"))
    )
    (net (code "25") (name "Net-(5I--1)") (class "Default")
      (node (ref "5I") (pin "P1") (pinfunction "-1_P1") (pintype "bidirectional"))
      (node (ref "IN_4") (pin "P$2") (pinfunction "4_P$2") (pintype "passive"))
    )
    (net (code "26") (name "Net-(5I--2)") (class "Default")
      (node (ref "5I") (pin "P2") (pinfunction "-2_P2") (pintype "bidirectional"))
      (node (ref "IN_3") (pin "P$2") (pinfunction "4_P$2") (pintype "passive"))
    )
    (net (code "27") (name "Net-(5I--4)") (class "Default")
      (node (ref "5I") (pin "P4") (pinfunction "-4_P4") (pintype "bidirectional"))
      (node (ref "IN_2") (pin "P$2") (pinfunction "4_P$2") (pintype "passive"))
    )
    (net (code "28") (name "Net-(5I--5)") (class "Default")
      (node (ref "5I") (pin "P5") (pinfunction "-5_P5") (pintype "bidirectional"))
      (node (ref "IN_1") (pin "P$2") (pinfunction "4_P$2") (pintype "passive"))
    )
    (net (code "29") (name "Net-(5O--1)") (class "Default")
      (node (ref "5O") (pin "P1") (pinfunction "-1_P1") (pintype "bidirectional"))
      (node (ref "IC2") (pin "12") (pinfunction "+IN_12") (pintype "input"))
      (node (ref "IN_1") (pin "P$3") (pinfunction "3_P$3") (pintype "passive"))
      (node (ref "R505") (pin "1") (pinfunction "1_1") (pintype "passive"))
    )
    (net (code "30") (name "Net-(5O--2)") (class "Default")
      (node (ref "5O") (pin "P2") (pinfunction "-2_P2") (pintype "bidirectional"))
      (node (ref "IC2") (pin "10") (pinfunction "+IN_10") (pintype "input"))
      (node (ref "IN_2") (pin "P$3") (pinfunction "3_P$3") (pintype "passive"))
      (node (ref "R506") (pin "1") (pinfunction "1_1") (pintype "passive"))
    )
    (net (code "31") (name "Net-(5O--4)") (class "Default")
      (node (ref "5O") (pin "P4") (pinfunction "-4_P4") (pintype "bidirectional"))
      (node (ref "IC2") (pin "5") (pinfunction "+IN_5") (pintype "input"))
      (node (ref "IN_3") (pin "P$3") (pinfunction "3_P$3") (pintype "passive"))
      (node (ref "R507") (pin "1") (pinfunction "1_1") (pintype "passive"))
    )
    (net (code "32") (name "Net-(5O--5)") (class "Default")
      (node (ref "5O") (pin "P5") (pinfunction "-5_P5") (pintype "bidirectional"))
      (node (ref "IC2") (pin "3") (pinfunction "+IN_3") (pintype "input"))
      (node (ref "IN_4") (pin "P$3") (pinfunction "3_P$3") (pintype "passive"))
      (node (ref "R508") (pin "1") (pinfunction "1_1") (pintype "passive"))
    )
    (net (code "33") (name "Net-(140K1-Pad2)") (class "Default")
      (node (ref "140K1") (pin "2") (pinfunction "2_2") (pintype "passive"))
      (node (ref "R59") (pin "1") (pinfunction "1_1") (pintype "passive"))
      (node (ref "R61") (pin "1") (pinfunction "1_1") (pintype "passive"))
    )
    (net (code "34") (name "Net-(C5-Pad1)") (class "Default")
      (node (ref "C5") (pin "1") (pinfunction "1_1") (pintype "passive"))
      (node (ref "R12") (pin "1") (pinfunction "1_1") (pintype "passive"))
    )
    (net (code "35") (name "Net-(C7-Pad1)") (class "Default")
      (node (ref "C7") (pin "1") (pinfunction "1_1") (pintype "passive"))
      (node (ref "R60") (pin "1") (pinfunction "1_1") (pintype "passive"))
    )
    (net (code "36") (name "Net-(D1-K2)") (class "Default")
      (node (ref "D1") (pin "2") (pinfunction "K2_2") (pintype "passive"))
      (node (ref "IC5") (pin "11") (pinfunction "CTRL_11") (pintype "input"))
      (node (ref "R51") (pin "1") (pinfunction "1_1") (pintype "passive"))
    )
    (net (code "37") (name "Net-(IC1A--IN)") (class "Default")
      (node (ref "IC1") (pin "2") (pinfunction "-IN_2") (pintype "input"))
      (node (ref "R101") (pin "1") (pinfunction "1_1") (pintype "passive"))
      (node (ref "R102") (pin "1") (pinfunction "1_1") (pintype "passive"))
      (node (ref "R103") (pin "1") (pinfunction "1_1") (pintype "passive"))
      (node (ref "R104") (pin "1") (pinfunction "1_1") (pintype "passive"))
      (node (ref "R105") (pin "1") (pinfunction "1_1") (pintype "passive"))
      (node (ref "R106") (pin "1") (pinfunction "1_1") (pintype "passive"))
    )
    (net (code "38") (name "Net-(IC1A-OUT)") (class "Default")
      (node (ref "IC1") (pin "1") (pinfunction "OUT_1") (pintype "output"))
      (node (ref "R106") (pin "2") (pinfunction "2_2") (pintype "passive"))
      (node (ref "R107") (pin "1") (pinfunction "1_1") (pintype "passive"))
    )
    (net (code "39") (name "Net-(IC1B--IN)") (class "Default")
      (node (ref "IC1") (pin "6") (pinfunction "-IN_6") (pintype "input"))
      (node (ref "R107") (pin "2") (pinfunction "2_2") (pintype "passive"))
      (node (ref "R108") (pin "1") (pinfunction "1_1") (pintype "passive"))
    )
    (net (code "40") (name "Net-(IC1B-OUT)") (class "Default")
      (node (ref "IC1") (pin "7") (pinfunction "OUT_7") (pintype "output"))
      (node (ref "R108") (pin "2") (pinfunction "2_2") (pintype "passive"))
      (node (ref "R110") (pin "1") (pinfunction "1_1") (pintype "passive"))
    )
    (net (code "41") (name "Net-(IC1C--IN)") (class "Default")
      (node (ref "IC1") (pin "9") (pinfunction "-IN_9") (pintype "input"))
      (node (ref "R207") (pin "2") (pinfunction "2_2") (pintype "passive"))
      (node (ref "R208") (pin "1") (pinfunction "1_1") (pintype "passive"))
    )
    (net (code "42") (name "Net-(IC1C-OUT)") (class "Default")
      (node (ref "IC1") (pin "8") (pinfunction "OUT_8") (pintype "output"))
      (node (ref "R208") (pin "2") (pinfunction "2_2") (pintype "passive"))
      (node (ref "R210") (pin "1") (pinfunction "1_1") (pintype "passive"))
    )
    (net (code "43") (name "Net-(IC1D--IN)") (class "Default")
      (node (ref "IC1") (pin "13") (pinfunction "-IN_13") (pintype "input"))
      (node (ref "R201") (pin "1") (pinfunction "1_1") (pintype "passive"))
      (node (ref "R202") (pin "1") (pinfunction "1_1") (pintype "passive"))
      (node (ref "R203") (pin "1") (pinfunction "1_1") (pintype "passive"))
      (node (ref "R204") (pin "1") (pinfunction "1_1") (pintype "passive"))
      (node (ref "R205") (pin "1") (pinfunction "1_1") (pintype "passive"))
      (node (ref "R206") (pin "1") (pinfunction "1_1") (pintype "passive"))
    )
    (net (code "44") (name "Net-(IC1D-OUT)") (class "Default")
      (node (ref "IC1") (pin "14") (pinfunction "OUT_14") (pintype "output"))
      (node (ref "R206") (pin "2") (pinfunction "2_2") (pintype "passive"))
      (node (ref "R207") (pin "1") (pinfunction "1_1") (pintype "passive"))
    )
    (net (code "45") (name "Net-(IC3D-IN)") (class "Default")
      (node (ref "IC3") (pin "15") (pinfunction "IN_15") (pintype "input"))
      (node (ref "R59") (pin "2") (pinfunction "2_2") (pintype "passive"))
      (node (ref "R60") (pin "2") (pinfunction "2_2") (pintype "passive"))
    )
    (net (code "46") (name "Net-(IC3D-OUT)") (class "Default")
      (node (ref "C6") (pin "2") (pinfunction "2_2") (pintype "passive"))
      (node (ref "IC3") (pin "13") (pinfunction "OUT_13") (pintype "output"))
      (node (ref "IC7") (pin "13") (pinfunction "-IN_13") (pintype "input"))
      (node (ref "R58") (pin "1") (pinfunction "1_1") (pintype "passive"))
    )
    (net (code "47") (name "Net-(IC4B-+IN)") (class "Default")
      (node (ref "C3") (pin "1") (pinfunction "1_1") (pintype "passive"))
      (node (ref "IC4") (pin "5") (pinfunction "+IN_5") (pintype "input"))
      (node (ref "OFFSET_LINA") (pin "2") (pinfunction "S_2") (pintype "passive"))
    )
    (net (code "48") (name "Net-(IC5C-IN)") (class "Default")
      (node (ref "IC5") (pin "10") (pinfunction "IN_10") (pintype "input"))
      (node (ref "R12") (pin "2") (pinfunction "2_2") (pintype "passive"))
      (node (ref "R6") (pin "2") (pinfunction "2_2") (pintype "passive"))
    )
    (net (code "49") (name "Net-(IC5C-OUT)") (class "Default")
      (node (ref "C12") (pin "2") (pinfunction "2_2") (pintype "passive"))
      (node (ref "IC5") (pin "12") (pinfunction "OUT_12") (pintype "output"))
      (node (ref "IC6") (pin "9") (pinfunction "-IN_9") (pintype "input"))
      (node (ref "R36") (pin "1") (pinfunction "1_1") (pintype "passive"))
    )
    (net (code "50") (name "Net-(IC6A-+IN)") (class "Default")
      (node (ref "IC6") (pin "3") (pinfunction "+IN_3") (pintype "input"))
      (node (ref "R14") (pin "1") (pinfunction "1_1") (pintype "passive"))
      (node (ref "R16") (pin "2") (pinfunction "2_2") (pintype "passive"))
    )
    (net (code "51") (name "Net-(IC6A--IN)") (class "Default")
      (node (ref "IC6") (pin "2") (pinfunction "-IN_2") (pintype "input"))
      (node (ref "R19") (pin "1") (pinfunction "1_1") (pintype "passive"))
      (node (ref "R20") (pin "2") (pinfunction "2_2") (pintype "passive"))
    )
    (net (code "52") (name "Net-(IC7B--IN)") (class "Default")
      (node (ref "IC7") (pin "6") (pinfunction "-IN_6") (pintype "input"))
      (node (ref "R18") (pin "1") (pinfunction "1_1") (pintype "passive"))
      (node (ref "R55") (pin "2") (pinfunction "2_2") (pintype "passive"))
    )
    (net (code "53") (name "Net-(IC7B-OUT)") (class "Default")
      (node (ref "IC7") (pin "7") (pinfunction "OUT_7") (pintype "output"))
      (node (ref "R18") (pin "2") (pinfunction "2_2") (pintype "passive"))
      (node (ref "R58") (pin "2") (pinfunction "2_2") (pintype "passive"))
    )
    (net (code "54") (name "Net-(IC8A-+IN)") (class "Default")
      (node (ref "IC8") (pin "3") (pinfunction "+IN_3") (pintype "input"))
      (node (ref "R21") (pin "1") (pinfunction "1_1") (pintype "passive"))
      (node (ref "R22") (pin "2") (pinfunction "2_2") (pintype "passive"))
    )
    (net (code "55") (name "Net-(IC8A--IN)") (class "Default")
      (node (ref "IC8") (pin "2") (pinfunction "-IN_2") (pintype "input"))
      (node (ref "R23") (pin "1") (pinfunction "1_1") (pintype "passive"))
      (node (ref "R24") (pin "2") (pinfunction "2_2") (pintype "passive"))
    )
    (net (code "56") (name "Net-(IC9A-+IN)") (class "Default")
      (node (ref "IC9") (pin "3") (pinfunction "+IN_3") (pintype "input"))
      (node (ref "R28") (pin "1") (pinfunction "1_1") (pintype "passive"))
      (node (ref "R29") (pin "2") (pinfunction "2_2") (pintype "passive"))
    )
    (net (code "57") (name "Net-(IC9A--IN)") (class "Default")
      (node (ref "IC9") (pin "2") (pinfunction "-IN_2") (pintype "input"))
      (node (ref "R30") (pin "1") (pinfunction "1_1") (pintype "passive"))
      (node (ref "R31") (pin "2") (pinfunction "2_2") (pintype "passive"))
    )
    (net (code "58") (name "Net-(IC14A--IN)") (class "Default")
      (node (ref "IC14") (pin "2") (pinfunction "-IN_2") (pintype "input"))
      (node (ref "R39") (pin "2") (pinfunction "2_2") (pintype "passive"))
      (node (ref "R42") (pin "1") (pinfunction "1_1") (pintype "passive"))
    )
    (net (code "59") (name "Net-(IC14A-OUT)") (class "Default")
      (node (ref "IC14") (pin "1") (pinfunction "OUT_1") (pintype "output"))
      (node (ref "R15") (pin "2") (pinfunction "2_2") (pintype "passive"))
      (node (ref "R39") (pin "1") (pinfunction "1_1") (pintype "passive"))
    )
    (net (code "60") (name "Net-(IC14B-+IN)") (class "Default")
      (node (ref "IC14") (pin "5") (pinfunction "+IN_5") (pintype "input"))
      (node (ref "R26") (pin "1") (pinfunction "1_1") (pintype "passive"))
      (node (ref "R27") (pin "1") (pinfunction "1_1") (pintype "passive"))
    )
    (net (code "61") (name "Net-(IC14B--IN)") (class "Default")
      (node (ref "IC14") (pin "6") (pinfunction "-IN_6") (pintype "input"))
      (node (ref "R15") (pin "1") (pinfunction "1_1") (pintype "passive"))
      (node (ref "R38") (pin "2") (pinfunction "2_2") (pintype "passive"))
      (node (ref "R5") (pin "1") (pinfunction "1_1") (pintype "passive"))
    )
    (net (code "62") (name "Net-(IC14D--IN)") (class "Default")
      (node (ref "IC14") (pin "13") (pinfunction "-IN_13") (pintype "input"))
      (node (ref "R17") (pin "1") (pinfunction "1_1") (pintype "passive"))
      (node (ref "R25") (pin "2") (pinfunction "2_2") (pintype "passive"))
    )
    (net (code "63") (name "Net-(OFFSET_LINA-E)") (class "Default")
      (node (ref "OFFSET_LINA") (pin "3") (pinfunction "E_3") (pintype "passive"))
      (node (ref "R13") (pin "1") (pinfunction "1_1") (pintype "passive"))
    )
    (net (code "64") (name "Net-(OFFSET_REF-E)") (class "Default")
      (node (ref "OFFSET_REF") (pin "3") (pinfunction "E_3") (pintype "passive"))
      (node (ref "R3") (pin "1") (pinfunction "1_1") (pintype "passive"))
    )
    (net (code "65") (name "Net-(OFFSET_REF-S)") (class "Default")
      (node (ref "C9") (pin "1") (pinfunction "1_1") (pintype "passive"))
      (node (ref "OFFSET_REF") (pin "2") (pinfunction "S_2") (pintype "passive"))
      (node (ref "R17") (pin "2") (pinfunction "2_2") (pintype "passive"))
    )
    (net (code "66") (name "Net-(OUT_A+-3)") (class "Default")
      (node (ref "OUT_A+") (pin "P$3") (pinfunction "3_P$3") (pintype "passive"))
      (node (ref "R110") (pin "2") (pinfunction "2_2") (pintype "passive"))
    )
    (net (code "67") (name "Net-(OUT_B+-3)") (class "Default")
      (node (ref "OUT_B+") (pin "P$3") (pinfunction "3_P$3") (pintype "passive"))
      (node (ref "R210") (pin "2") (pinfunction "2_2") (pintype "passive"))
    )
    (net (code "68") (name "Net-(POT1A-Pad2)") (class "Default")
      (node (ref "POT1A") (pin "2") (pinfunction "2_2") (pintype "bidirectional"))
      (node (ref "R1") (pin "1") (pinfunction "1_1") (pintype "passive"))
      (node (ref "R101") (pin "2") (pinfunction "2_2") (pintype "passive"))
    )
    (net (code "69") (name "Net-(POT1A-Pad3)") (class "Default")
      (node (ref "POT1A") (pin "3") (pinfunction "3_3") (pintype "bidirectional"))
      (node (ref "POT1B") (pin "3") (pinfunction "3_3") (pintype "bidirectional"))
    )
    (net (code "70") (name "Net-(POT1B-Pad2)") (class "Default")
      (node (ref "POT1B") (pin "2") (pinfunction "2_2") (pintype "bidirectional"))
      (node (ref "R11") (pin "1") (pinfunction "1_1") (pintype "passive"))
      (node (ref "R201") (pin "2") (pinfunction "2_2") (pintype "passive"))
    )
    (net (code "71") (name "Net-(POT2A-Pad2)") (class "Default")
      (node (ref "POT2A") (pin "2") (pinfunction "2_2") (pintype "bidirectional"))
      (node (ref "R102") (pin "2") (pinfunction "2_2") (pintype "passive"))
      (node (ref "R2") (pin "1") (pinfunction "1_1") (pintype "passive"))
    )
    (net (code "72") (name "Net-(POT2A-Pad3)") (class "Default")
      (node (ref "POT2A") (pin "3") (pinfunction "3_3") (pintype "bidirectional"))
      (node (ref "POT2B") (pin "3") (pinfunction "3_3") (pintype "bidirectional"))
    )
    (net (code "73") (name "Net-(POT2B-Pad2)") (class "Default")
      (node (ref "POT2B") (pin "2") (pinfunction "2_2") (pintype "bidirectional"))
      (node (ref "R202") (pin "2") (pinfunction "2_2") (pintype "passive"))
      (node (ref "R8") (pin "1") (pinfunction "1_1") (pintype "passive"))
    )
    (net (code "74") (name "Net-(POT3A-Pad2)") (class "Default")
      (node (ref "POT3A") (pin "2") (pinfunction "2_2") (pintype "bidirectional"))
      (node (ref "R103") (pin "2") (pinfunction "2_2") (pintype "passive"))
      (node (ref "R4") (pin "1") (pinfunction "1_1") (pintype "passive"))
    )
    (net (code "75") (name "Net-(POT3A-Pad3)") (class "Default")
      (node (ref "POT3A") (pin "3") (pinfunction "3_3") (pintype "bidirectional"))
      (node (ref "POT3B") (pin "3") (pinfunction "3_3") (pintype "bidirectional"))
    )
    (net (code "76") (name "Net-(POT3B-Pad2)") (class "Default")
      (node (ref "POT3B") (pin "2") (pinfunction "2_2") (pintype "bidirectional"))
      (node (ref "R203") (pin "2") (pinfunction "2_2") (pintype "passive"))
      (node (ref "R9") (pin "1") (pinfunction "1_1") (pintype "passive"))
    )
    (net (code "77") (name "Net-(POT4A-Pad2)") (class "Default")
      (node (ref "POT4A") (pin "2") (pinfunction "2_2") (pintype "bidirectional"))
      (node (ref "R104") (pin "2") (pinfunction "2_2") (pintype "passive"))
      (node (ref "R7") (pin "1") (pinfunction "1_1") (pintype "passive"))
    )
    (net (code "78") (name "Net-(POT4A-Pad3)") (class "Default")
      (node (ref "POT4A") (pin "3") (pinfunction "3_3") (pintype "bidirectional"))
      (node (ref "POT4B") (pin "3") (pinfunction "3_3") (pintype "bidirectional"))
    )
    (net (code "79") (name "Net-(POT4B-Pad2)") (class "Default")
      (node (ref "POT4B") (pin "2") (pinfunction "2_2") (pintype "bidirectional"))
      (node (ref "R10") (pin "1") (pinfunction "1_1") (pintype "passive"))
      (node (ref "R204") (pin "2") (pinfunction "2_2") (pintype "passive"))
    )
    (net (code "80") (name "Net-(Q1-D)") (class "Default")
      (node (ref "Q1") (pin "3") (pinfunction "D_3") (pintype "passive"))
      (node (ref "SV1") (pin "10") (pinfunction "10_10") (pintype "passive"))
      (node (ref "SV1") (pin "9") (pinfunction "9_9") (pintype "passive"))
    )
    (net (code "81") (name "Net-(Q2-D)") (class "Default")
      (node (ref "Q2") (pin "3") (pinfunction "D_3") (pintype "passive"))
      (node (ref "SV1") (pin "1") (pinfunction "1_1") (pintype "passive"))
      (node (ref "SV1") (pin "2") (pinfunction "2_2") (pintype "passive"))
    )
    (net (code "82") (name "Net-(R1-Pad2)") (class "Default")
      (node (ref "R1") (pin "2") (pinfunction "2_2") (pintype "passive"))
      (node (ref "SJ1") (pin "2") (pinfunction "2_2") (pintype "passive"))
    )
    (net (code "83") (name "Net-(R2-Pad2)") (class "Default")
      (node (ref "R2") (pin "2") (pinfunction "2_2") (pintype "passive"))
      (node (ref "SJ2") (pin "2") (pinfunction "2_2") (pintype "passive"))
    )
    (net (code "84") (name "Net-(R4-Pad2)") (class "Default")
      (node (ref "R4") (pin "2") (pinfunction "2_2") (pintype "passive"))
      (node (ref "SJ3") (pin "2") (pinfunction "2_2") (pintype "passive"))
    )
    (net (code "85") (name "Net-(R7-Pad2)") (class "Default")
      (node (ref "R7") (pin "2") (pinfunction "2_2") (pintype "passive"))
      (node (ref "SJ4") (pin "2") (pinfunction "2_2") (pintype "passive"))
    )
    (net (code "86") (name "Net-(R8-Pad2)") (class "Default")
      (node (ref "R8") (pin "2") (pinfunction "2_2") (pintype "passive"))
      (node (ref "SJ6") (pin "2") (pinfunction "2_2") (pintype "passive"))
    )
    (net (code "87") (name "Net-(R9-Pad2)") (class "Default")
      (node (ref "R9") (pin "2") (pinfunction "2_2") (pintype "passive"))
      (node (ref "SJ7") (pin "2") (pinfunction "2_2") (pintype "passive"))
    )
    (net (code "88") (name "Net-(R10-Pad2)") (class "Default")
      (node (ref "R10") (pin "2") (pinfunction "2_2") (pintype "passive"))
      (node (ref "SJ8") (pin "2") (pinfunction "2_2") (pintype "passive"))
    )
    (net (code "89") (name "Net-(R11-Pad2)") (class "Default")
      (node (ref "R11") (pin "2") (pinfunction "2_2") (pintype "passive"))
      (node (ref "SJ5") (pin "2") (pinfunction "2_2") (pintype "passive"))
    )
    (net (code "90") (name "unconnected-(D1-K1-Pad1)") (class "Default")
      (node (ref "D1") (pin "1") (pinfunction "K1_1") (pintype "passive"))
    )
  )
)
